# Tiny841.net
KiCad netlist of a schematic drawn in EAGLE
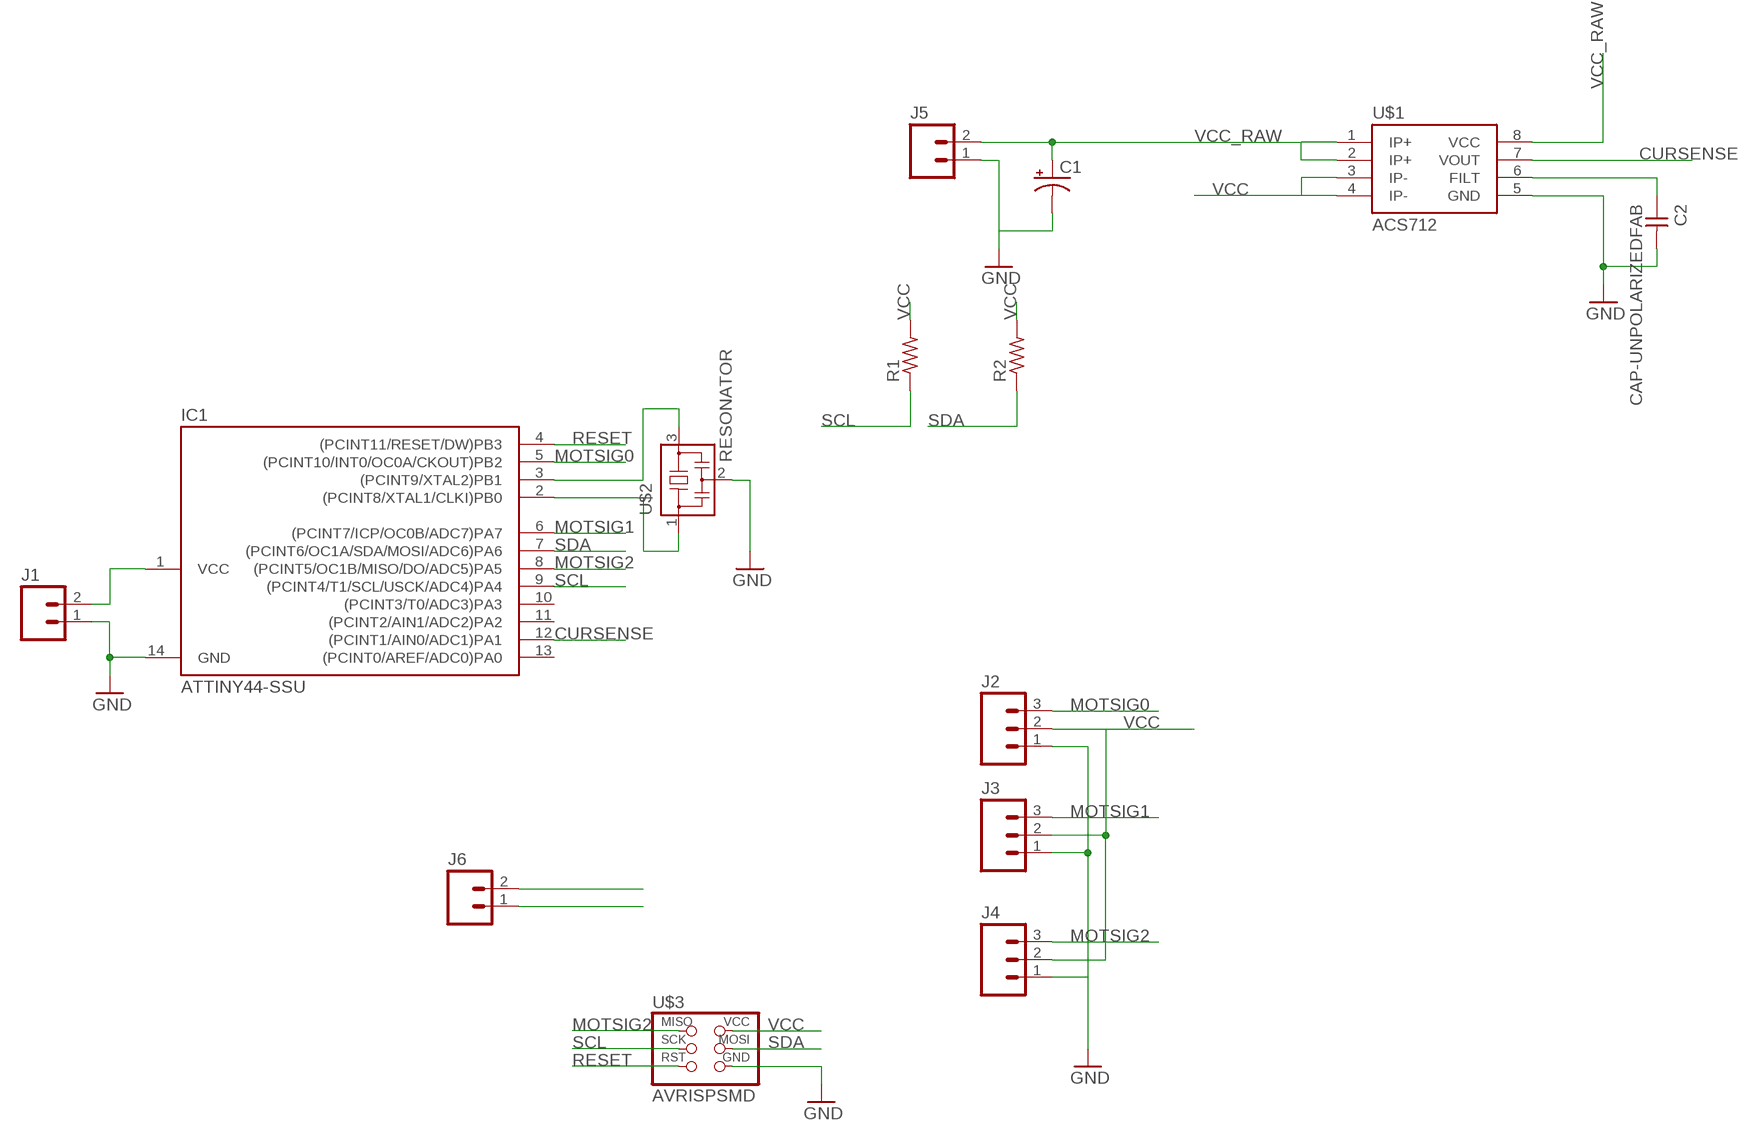
[diagram p0: schematic, sheet 1]

(export (version "E")
  (design (tool "Eeschema 10.0.6"))
  (components
    (comp (ref "C1")
      (value "47UF-50V-20%(ELECT)")
      (footprint "eagle-import:PANASONIC_D")
      (libsource (lib "eagle-import") (part "47UF-50V-20%(ELECT)"))
    )
    (comp (ref "C2")
      (value "CAP-UNPOLARIZEDFAB")
      (footprint "eagle-import:C1206FAB")
      (libsource (lib "eagle-import") (part "CAP-UNPOLARIZEDFAB"))
    )
    (comp (ref "IC1")
      (value "ATTINY44-SSU")
      (footprint "eagle-import:SOIC14")
      (libsource (lib "eagle-import") (part "ATTINY44-SSU"))
    )
    (comp (ref "J1")
      (value "M02PTH")
      (footprint "eagle-import:1X02")
      (libsource (lib "eagle-import") (part "M02PTH"))
    )
    (comp (ref "J2")
      (value "M03PTH")
      (footprint "eagle-import:1X03")
      (libsource (lib "eagle-import") (part "M03PTH"))
    )
    (comp (ref "J3")
      (value "M03PTH")
      (footprint "eagle-import:1X03")
      (libsource (lib "eagle-import") (part "M03PTH"))
    )
    (comp (ref "J4")
      (value "M03PTH")
      (footprint "eagle-import:1X03")
      (libsource (lib "eagle-import") (part "M03PTH"))
    )
    (comp (ref "J5")
      (value "M023.5MM-NO_SILK")
      (footprint "eagle-import:SCREWTERMINAL-3.5MM-2-NS")
      (libsource (lib "eagle-import") (part "M023.5MM-NO_SILK"))
    )
    (comp (ref "J6")
      (value "M02PTH")
      (footprint "eagle-import:1X02")
      (libsource (lib "eagle-import") (part "M02PTH"))
    )
    (comp (ref "R1")
      (value "RES-US1206FAB")
      (footprint "eagle-import:R1206FAB")
      (libsource (lib "eagle-import") (part "RES-US1206FAB"))
    )
    (comp (ref "R2")
      (value "RES-US1206FAB")
      (footprint "eagle-import:R1206FAB")
      (libsource (lib "eagle-import") (part "RES-US1206FAB"))
    )
    (comp (ref "U$1")
      (value "ACS712")
      (footprint "eagle-import:SO08")
      (libsource (lib "eagle-import") (part "ACS712"))
    )
    (comp (ref "U$2")
      (value "RESONATOR")
      (footprint "eagle-import:EFOBM")
      (libsource (lib "eagle-import") (part "RESONATOR"))
    )
    (comp (ref "U$3")
      (value "AVRISPSMD")
      (footprint "eagle-import:2X03SMD")
      (libsource (lib "eagle-import") (part "AVRISPSMD"))
    )
  )
  (nets
    (net (code "1") (name "/CURSENSE") (class "Default")
      (node (ref "IC1") (pin "12") (pinfunction "(PCINT1/AIN0/ADC1)PA1_12") (pintype "bidirectional"))
      (node (ref "U$1") (pin "7") (pinfunction "VOUT_7") (pintype "bidirectional"))
    )
    (net (code "2") (name "/MOTSIG0") (class "Default")
      (node (ref "IC1") (pin "5") (pinfunction "(PCINT10/INT0/OC0A/CKOUT)PB2_5") (pintype "bidirectional"))
      (node (ref "J2") (pin "3") (pinfunction "3_3") (pintype "passive"))
    )
    (net (code "3") (name "/MOTSIG1") (class "Default")
      (node (ref "IC1") (pin "6") (pinfunction "(PCINT7/ICP/OC0B/ADC7)PA7_6") (pintype "bidirectional"))
      (node (ref "J3") (pin "3") (pinfunction "3_3") (pintype "passive"))
    )
    (net (code "4") (name "/MOTSIG2") (class "Default")
      (node (ref "IC1") (pin "8") (pinfunction "(PCINT5/OC1B/MISO/DO/ADC5)PA5_8") (pintype "bidirectional"))
      (node (ref "J4") (pin "3") (pinfunction "3_3") (pintype "passive"))
      (node (ref "U$3") (pin "1") (pinfunction "MISO_1") (pintype "passive"))
    )
    (net (code "5") (name "/RESET") (class "Default")
      (node (ref "IC1") (pin "4") (pinfunction "(PCINT11/RESET/DW)PB3_4") (pintype "bidirectional"))
      (node (ref "U$3") (pin "5") (pinfunction "RST_5") (pintype "passive"))
    )
    (net (code "6") (name "/SCL") (class "Default")
      (node (ref "IC1") (pin "9") (pinfunction "(PCINT4/T1/SCL/USCK/ADC4)PA4_9") (pintype "bidirectional"))
      (node (ref "J6") (pin "1") (pinfunction "1_1") (pintype "passive"))
      (node (ref "R1") (pin "1") (pinfunction "1_1") (pintype "passive"))
      (node (ref "U$3") (pin "3") (pinfunction "SCK_3") (pintype "passive"))
    )
    (net (code "7") (name "/SDA") (class "Default")
      (node (ref "IC1") (pin "7") (pinfunction "(PCINT6/OC1A/SDA/MOSI/ADC6)PA6_7") (pintype "bidirectional"))
      (node (ref "J6") (pin "2") (pinfunction "2_2") (pintype "passive"))
      (node (ref "R2") (pin "1") (pinfunction "1_1") (pintype "passive"))
      (node (ref "U$3") (pin "4") (pinfunction "MOSI_4") (pintype "passive"))
    )
    (net (code "8") (name "/VCC") (class "Default")
      (node (ref "IC1") (pin "1") (pinfunction "VCC_1") (pintype "power_in"))
      (node (ref "J1") (pin "2") (pinfunction "2_2") (pintype "passive"))
      (node (ref "J2") (pin "2") (pinfunction "2_2") (pintype "passive"))
      (node (ref "J3") (pin "2") (pinfunction "2_2") (pintype "passive"))
      (node (ref "J4") (pin "2") (pinfunction "2_2") (pintype "passive"))
      (node (ref "R1") (pin "2") (pinfunction "2_2") (pintype "passive"))
      (node (ref "R2") (pin "2") (pinfunction "2_2") (pintype "passive"))
      (node (ref "U$1") (pin "3") (pinfunction "IP-_3") (pintype "bidirectional"))
      (node (ref "U$1") (pin "4") (pinfunction "IP-_4") (pintype "bidirectional"))
      (node (ref "U$3") (pin "2") (pinfunction "VCC_2") (pintype "passive"))
    )
    (net (code "9") (name "/VCC_RAW") (class "Default")
      (node (ref "C1") (pin "+") (pinfunction "+_+") (pintype "passive"))
      (node (ref "J5") (pin "2") (pinfunction "2_2") (pintype "passive"))
      (node (ref "U$1") (pin "1") (pinfunction "IP+_1") (pintype "bidirectional"))
      (node (ref "U$1") (pin "2") (pinfunction "IP+_2") (pintype "bidirectional"))
      (node (ref "U$1") (pin "8") (pinfunction "VCC_8") (pintype "bidirectional"))
    )
    (net (code "10") (name "GND") (class "Default")
      (node (ref "C1") (pin "-") (pinfunction "-_-") (pintype "passive"))
      (node (ref "C2") (pin "2") (pinfunction "2_2") (pintype "passive"))
      (node (ref "IC1") (pin "14") (pinfunction "GND_14") (pintype "power_in"))
      (node (ref "J1") (pin "1") (pinfunction "1_1") (pintype "passive"))
      (node (ref "J2") (pin "1") (pinfunction "1_1") (pintype "passive"))
      (node (ref "J3") (pin "1") (pinfunction "1_1") (pintype "passive"))
      (node (ref "J4") (pin "1") (pinfunction "1_1") (pintype "passive"))
      (node (ref "J5") (pin "1") (pinfunction "1_1") (pintype "passive"))
      (node (ref "U$1") (pin "5") (pinfunction "GND_5") (pintype "bidirectional"))
      (node (ref "U$2") (pin "2") (pinfunction "2_2") (pintype "passive"))
      (node (ref "U$3") (pin "6") (pinfunction "GND_6") (pintype "passive"))
    )
    (net (code "11") (name "Net-(IC1-(PCINT8{slash}XTAL1{slash}CLKI)PB0)") (class "Default")
      (node (ref "IC1") (pin "2") (pinfunction "(PCINT8/XTAL1/CLKI)PB0_2") (pintype "bidirectional"))
      (node (ref "U$2") (pin "1") (pinfunction "1_1") (pintype "passive"))
    )
    (net (code "12") (name "Net-(IC1-(PCINT9{slash}XTAL2)PB1)") (class "Default")
      (node (ref "IC1") (pin "3") (pinfunction "(PCINT9/XTAL2)PB1_3") (pintype "bidirectional"))
      (node (ref "U$2") (pin "3") (pinfunction "3_3") (pintype "passive"))
    )
    (net (code "13") (name "Net-(U$1-FILT)") (class "Default")
      (node (ref "C2") (pin "1") (pinfunction "1_1") (pintype "passive"))
      (node (ref "U$1") (pin "6") (pinfunction "FILT_6") (pintype "bidirectional"))
    )
    (net (code "14") (name "unconnected-(IC1-(PCINT0{slash}AREF{slash}ADC0)PA0-Pad13)") (class "Default")
      (node (ref "IC1") (pin "13") (pinfunction "(PCINT0/AREF/ADC0)PA0_13") (pintype "bidirectional"))
    )
    (net (code "15") (name "unconnected-(IC1-(PCINT2{slash}AIN1{slash}ADC2)PA2-Pad11)") (class "Default")
      (node (ref "IC1") (pin "11") (pinfunction "(PCINT2/AIN1/ADC2)PA2_11") (pintype "bidirectional"))
    )
    (net (code "16") (name "unconnected-(IC1-(PCINT3{slash}T0{slash}ADC3)PA3-Pad10)") (class "Default")
      (node (ref "IC1") (pin "10") (pinfunction "(PCINT3/T0/ADC3)PA3_10") (pintype "bidirectional"))
    )
  )
)
